# Relay.net
KiCad netlist of a schematic drawn in Altium Designer
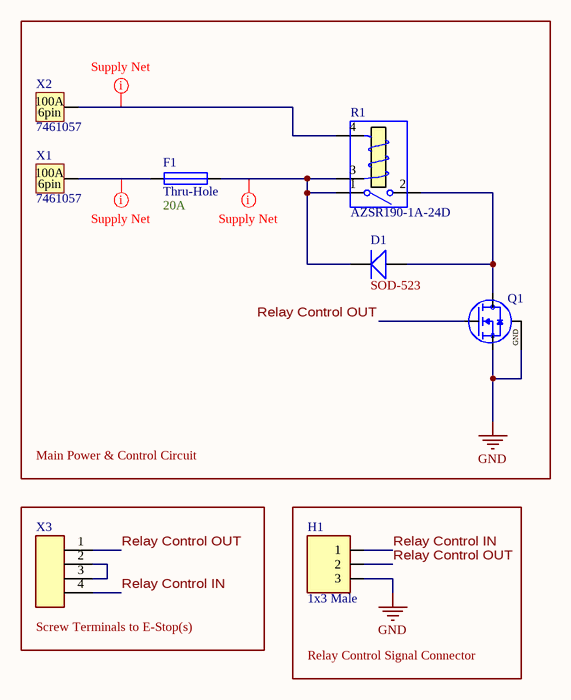
[diagram p0: Relay.SchDoc]

(export (version "E")
  (design (tool "Eeschema 10.0.6"))
  (components
    (comp (ref "D1")
      (value "Rectifier")
      (footprint "[Diode] SMD SOD-523")
      (description "Generic")
      (fields (field (name "SIZE PACKAGE") "SOD-523"))
      (libsource (lib "RADM Components") (part "[Diode] SMD Rectifier"))
    )
    (comp (ref "F1")
      (value "Thru-Hole")
      (footprint "[Fuse] Blade (2)")
      (fields (field (name "CAPACITY") "20A"))
      (libsource (lib "RADM Components") (part "[Fuse] Thru-Hole Blade"))
    )
    (comp (ref "H1")
      (value "1x3 Male")
      (footprint "[Header] Shrouded 1x3 Male")
      (description "070543-0037\r\nMates with 005057-9403")
      (libsource (lib "RADM Connectors") (part "[Header] Shrouded 1x3 Male"))
    )
    (comp (ref "Q1")
      (value "[FET] NMOS IRF610PBF")
      (footprint "[FET] NMOS IRF610PBF")
      (description "N-Channel 200 V 3.3A (Tc) 36W (Tc) Through Hole TO-220AB")
      (libsource (lib "RADM Components") (part "[FET] NMOS IRF610PBF"))
    )
    (comp (ref "R1")
      (value "AZSR190-1A-24D")
      (footprint "[Relay] AZSR190-1A-24D")
      (libsource (lib "RADM Components") (part "[Relay] AZSR190-1A-24D"))
    )
    (comp (ref "X1")
      (value "7461057")
      (footprint "[Port] Shank Connector (100A)")
      (description "7461057, internal thread")
      (libsource (lib "RADM Connectors") (part "[Port] Shank Connector (100A)"))
    )
    (comp (ref "X2")
      (value "7461057")
      (footprint "[Port] Shank Connector (100A)")
      (description "7461057, internal thread")
      (libsource (lib "RADM Connectors") (part "[Port] Shank Connector (100A)"))
    )
    (comp (ref "X3")
      (value "4pin Screw Terminal")
      (footprint "[Screw Terminal] 4pin 5mm")
      (libsource (lib "RADM Connectors") (part "[Screw Terminal] 4pin"))
    )
  )
  (nets
    (net (code "1") (name "/Relay Control IN") (class "Default")
      (node (ref "H1") (pin "1") (pinfunction "1_1") (pintype "passive"))
      (node (ref "X3") (pin "4") (pintype "power_in"))
    )
    (net (code "2") (name "/Relay Control OUT") (class "Default")
      (node (ref "H1") (pin "2") (pinfunction "2_2") (pintype "passive"))
      (node (ref "Q1") (pin "G") (pinfunction "Gate_G") (pintype "passive"))
      (node (ref "X3") (pin "1") (pintype "power_in"))
    )
    (net (code "3") (name "GND") (class "Default")
      (node (ref "H1") (pin "3") (pinfunction "3_3") (pintype "passive"))
      (node (ref "Q1") (pin "S") (pinfunction "Source_S") (pintype "passive"))
      (node (ref "Q1") (pin "X") (pinfunction "GND_X") (pintype "passive"))
    )
    (net (code "4") (name "Net-(D1-Anode)") (class "Default")
      (node (ref "D1") (pin "2") (pinfunction "Anode_2") (pintype "power_in"))
      (node (ref "Q1") (pin "D") (pinfunction "Drain_D") (pintype "passive"))
      (node (ref "R1") (pin "2") (pinfunction "2_2") (pintype "passive"))
    )
    (net (code "5") (name "Net-(D1-Cathode)") (class "Default")
      (node (ref "D1") (pin "1") (pinfunction "Cathode_1") (pintype "power_in"))
      (node (ref "F1") (pin "2") (pinfunction "2_2") (pintype "passive"))
      (node (ref "R1") (pin "1") (pinfunction "1_1") (pintype "passive"))
      (node (ref "R1") (pin "3") (pinfunction "T1_3") (pintype "passive"))
    )
    (net (code "6") (name "Net-(R1-T2)") (class "Default")
      (node (ref "R1") (pin "4") (pinfunction "T2_4") (pintype "passive"))
      (node (ref "X2") (pin "1") (pinfunction "4_1") (pintype "power_in"))
    )
    (net (code "7") (name "Net-(X1-4)") (class "Default")
      (node (ref "F1") (pin "1") (pinfunction "1_1") (pintype "passive"))
      (node (ref "X1") (pin "1") (pinfunction "4_1") (pintype "power_in"))
    )
    (net (code "8") (name "Net-(X3-Pad2)") (class "Default")
      (node (ref "X3") (pin "2") (pintype "power_in"))
      (node (ref "X3") (pin "3") (pintype "power_in"))
    )
  )
)
